# detector00.net
KiCad netlist of a schematic drawn in EAGLE
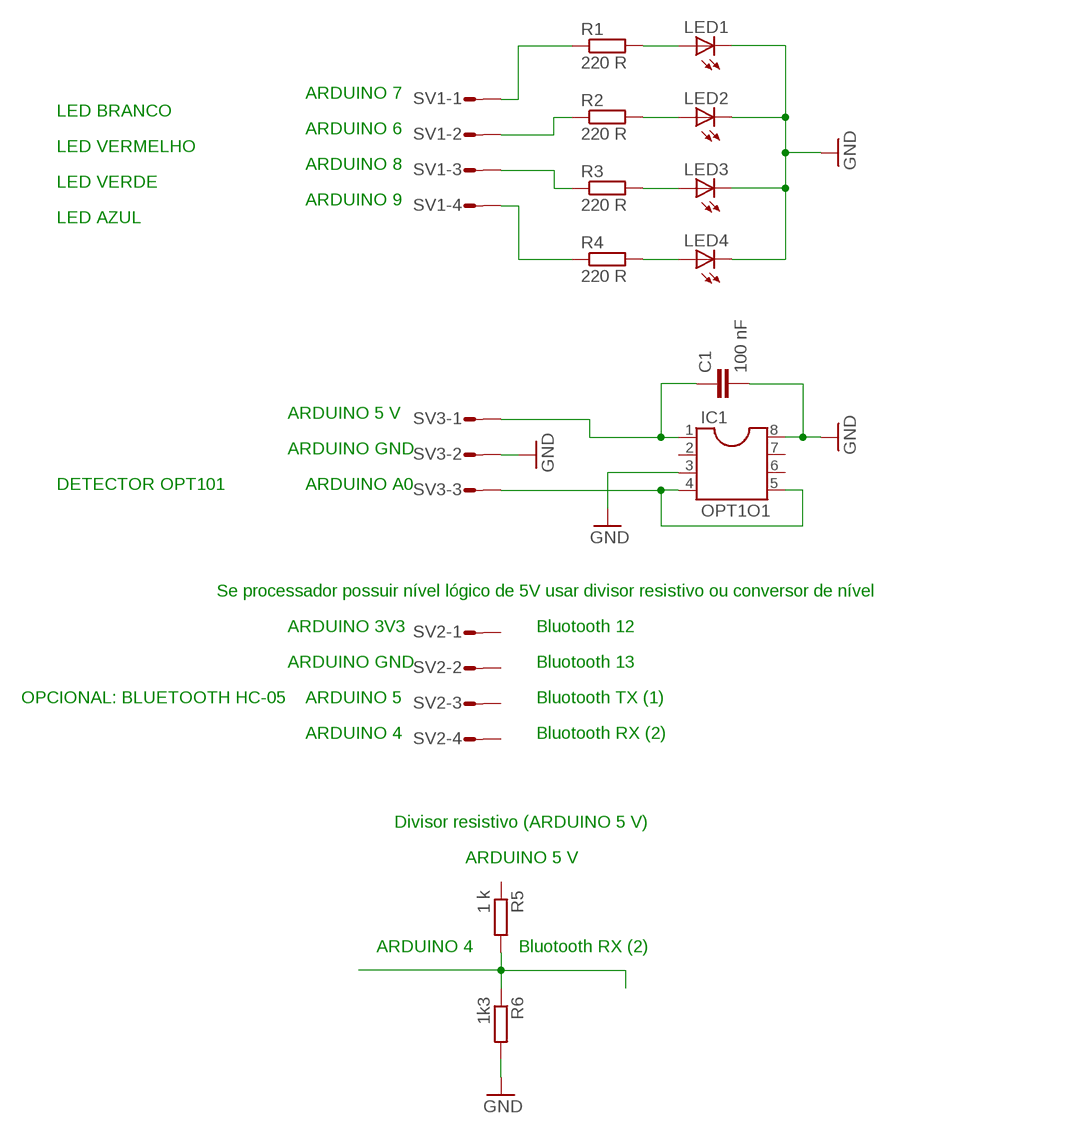
[diagram p0: schematic, sheet 1]

(export (version "E")
  (design (tool "Eeschema 10.0.6"))
  (components
    (comp (ref "C1")
      (value "100 nF")
      (footprint "eagle-import:C050-035X075")
      (libsource (lib "eagle-import") (part "C-EU050-035X075"))
    )
    (comp (ref "IC1")
      (value "OPT1O1")
      (footprint "eagle-import:DIL08")
      (libsource (lib "eagle-import") (part "DIL8"))
    )
    (comp (ref "LED1")
      (value "LED5MM")
      (footprint "eagle-import:LED5MM")
      (libsource (lib "eagle-import") (part "LED5MM"))
    )
    (comp (ref "LED2")
      (value "LED5MM")
      (footprint "eagle-import:LED5MM")
      (libsource (lib "eagle-import") (part "LED5MM"))
    )
    (comp (ref "LED3")
      (value "LED5MM")
      (footprint "eagle-import:LED5MM")
      (libsource (lib "eagle-import") (part "LED5MM"))
    )
    (comp (ref "LED4")
      (value "LED5MM")
      (footprint "eagle-import:LED5MM")
      (libsource (lib "eagle-import") (part "LED5MM"))
    )
    (comp (ref "R1")
      (value "220 R")
      (footprint "eagle-import:0204_7")
      (libsource (lib "eagle-import") (part "R-EU_0204/7"))
    )
    (comp (ref "R2")
      (value "220 R")
      (footprint "eagle-import:0204_7")
      (libsource (lib "eagle-import") (part "R-EU_0204/7"))
    )
    (comp (ref "R3")
      (value "220 R")
      (footprint "eagle-import:0204_7")
      (libsource (lib "eagle-import") (part "R-EU_0204/7"))
    )
    (comp (ref "R4")
      (value "220 R")
      (footprint "eagle-import:0204_7")
      (libsource (lib "eagle-import") (part "R-EU_0204/7"))
    )
    (comp (ref "R5")
      (value "1 k")
      (footprint "eagle-import:0204_7")
      (libsource (lib "eagle-import") (part "R-EU_0204/7"))
    )
    (comp (ref "R6")
      (value "1k3")
      (footprint "eagle-import:0204_7")
      (libsource (lib "eagle-import") (part "R-EU_0204/7"))
    )
    (comp (ref "SV1")
      (value "L04P")
      (footprint "eagle-import:L04P")
      (libsource (lib "eagle-import") (part "L04P"))
    )
    (comp (ref "SV2")
      (value "L04P")
      (footprint "eagle-import:L04P")
      (libsource (lib "eagle-import") (part "L04P"))
    )
    (comp (ref "SV3")
      (value "L04P")
      (footprint "eagle-import:L04P")
      (libsource (lib "eagle-import") (part "L04P"))
    )
  )
  (nets
    (net (code "1") (name "GND") (class "Default")
      (node (ref "C1") (pin "2") (pinfunction "2_2") (pintype "passive"))
      (node (ref "IC1") (pin "3") (pinfunction "3_3") (pintype "passive"))
      (node (ref "IC1") (pin "8") (pinfunction "8_8") (pintype "passive"))
      (node (ref "LED1") (pin "K") (pinfunction "C_K") (pintype "passive"))
      (node (ref "LED2") (pin "K") (pinfunction "C_K") (pintype "passive"))
      (node (ref "LED3") (pin "K") (pinfunction "C_K") (pintype "passive"))
      (node (ref "LED4") (pin "K") (pinfunction "C_K") (pintype "passive"))
      (node (ref "R6") (pin "2") (pinfunction "2_2") (pintype "passive"))
      (node (ref "SV3") (pin "2") (pinfunction "S_2") (pintype "passive"))
    )
    (net (code "2") (name "Net-(LED1-PadA)") (class "Default")
      (node (ref "LED1") (pin "A") (pinfunction "A_A") (pintype "passive"))
      (node (ref "R1") (pin "2") (pinfunction "2_2") (pintype "passive"))
    )
    (net (code "3") (name "Net-(LED2-PadA)") (class "Default")
      (node (ref "LED2") (pin "A") (pinfunction "A_A") (pintype "passive"))
      (node (ref "R2") (pin "2") (pinfunction "2_2") (pintype "passive"))
    )
    (net (code "4") (name "Net-(LED3-PadA)") (class "Default")
      (node (ref "LED3") (pin "A") (pinfunction "A_A") (pintype "passive"))
      (node (ref "R3") (pin "2") (pinfunction "2_2") (pintype "passive"))
    )
    (net (code "5") (name "Net-(LED4-PadA)") (class "Default")
      (node (ref "LED4") (pin "A") (pinfunction "A_A") (pintype "passive"))
      (node (ref "R4") (pin "2") (pinfunction "2_2") (pintype "passive"))
    )
    (net (code "6") (name "Net-(R5-Pad2)") (class "Default")
      (node (ref "R5") (pin "2") (pinfunction "2_2") (pintype "passive"))
      (node (ref "R6") (pin "1") (pinfunction "1_1") (pintype "passive"))
    )
    (net (code "7") (name "Net-(SV1A-S)") (class "Default")
      (node (ref "R1") (pin "1") (pinfunction "1_1") (pintype "passive"))
      (node (ref "SV1") (pin "1") (pinfunction "S_1") (pintype "passive"))
    )
    (net (code "8") (name "Net-(SV1B-S)") (class "Default")
      (node (ref "R2") (pin "1") (pinfunction "1_1") (pintype "passive"))
      (node (ref "SV1") (pin "2") (pinfunction "S_2") (pintype "passive"))
    )
    (net (code "9") (name "Net-(SV1C-S)") (class "Default")
      (node (ref "R3") (pin "1") (pinfunction "1_1") (pintype "passive"))
      (node (ref "SV1") (pin "3") (pinfunction "S_3") (pintype "passive"))
    )
    (net (code "10") (name "Net-(SV1D-S)") (class "Default")
      (node (ref "R4") (pin "1") (pinfunction "1_1") (pintype "passive"))
      (node (ref "SV1") (pin "4") (pinfunction "S_4") (pintype "passive"))
    )
    (net (code "11") (name "Net-(SV3A-S)") (class "Default")
      (node (ref "C1") (pin "1") (pinfunction "1_1") (pintype "passive"))
      (node (ref "IC1") (pin "1") (pinfunction "1_1") (pintype "passive"))
      (node (ref "SV3") (pin "1") (pinfunction "S_1") (pintype "passive"))
    )
    (net (code "12") (name "Net-(SV3C-S)") (class "Default")
      (node (ref "IC1") (pin "4") (pinfunction "4_4") (pintype "passive"))
      (node (ref "IC1") (pin "5") (pinfunction "5_5") (pintype "passive"))
      (node (ref "SV3") (pin "3") (pinfunction "S_3") (pintype "passive"))
    )
    (net (code "13") (name "unconnected-(IC1-Pad2)") (class "Default")
      (node (ref "IC1") (pin "2") (pinfunction "2_2") (pintype "passive"))
    )
    (net (code "14") (name "unconnected-(IC1-Pad6)") (class "Default")
      (node (ref "IC1") (pin "6") (pinfunction "6_6") (pintype "passive"))
    )
    (net (code "15") (name "unconnected-(IC1-Pad7)") (class "Default")
      (node (ref "IC1") (pin "7") (pinfunction "7_7") (pintype "passive"))
    )
    (net (code "16") (name "unconnected-(R5-Pad1)") (class "Default")
      (node (ref "R5") (pin "1") (pinfunction "1_1") (pintype "passive"))
    )
    (net (code "17") (name "unconnected-(SV2A-S-Pad1)") (class "Default")
      (node (ref "SV2") (pin "1") (pinfunction "S_1") (pintype "passive"))
    )
    (net (code "18") (name "unconnected-(SV2B-S-Pad2)") (class "Default")
      (node (ref "SV2") (pin "2") (pinfunction "S_2") (pintype "passive"))
    )
    (net (code "19") (name "unconnected-(SV2C-S-Pad3)") (class "Default")
      (node (ref "SV2") (pin "3") (pinfunction "S_3") (pintype "passive"))
    )
    (net (code "20") (name "unconnected-(SV2D-S-Pad4)") (class "Default")
      (node (ref "SV2") (pin "4") (pinfunction "S_4") (pintype "passive"))
    )
  )
)
